# node_v2.net
KiCad netlist of a schematic drawn in EAGLE
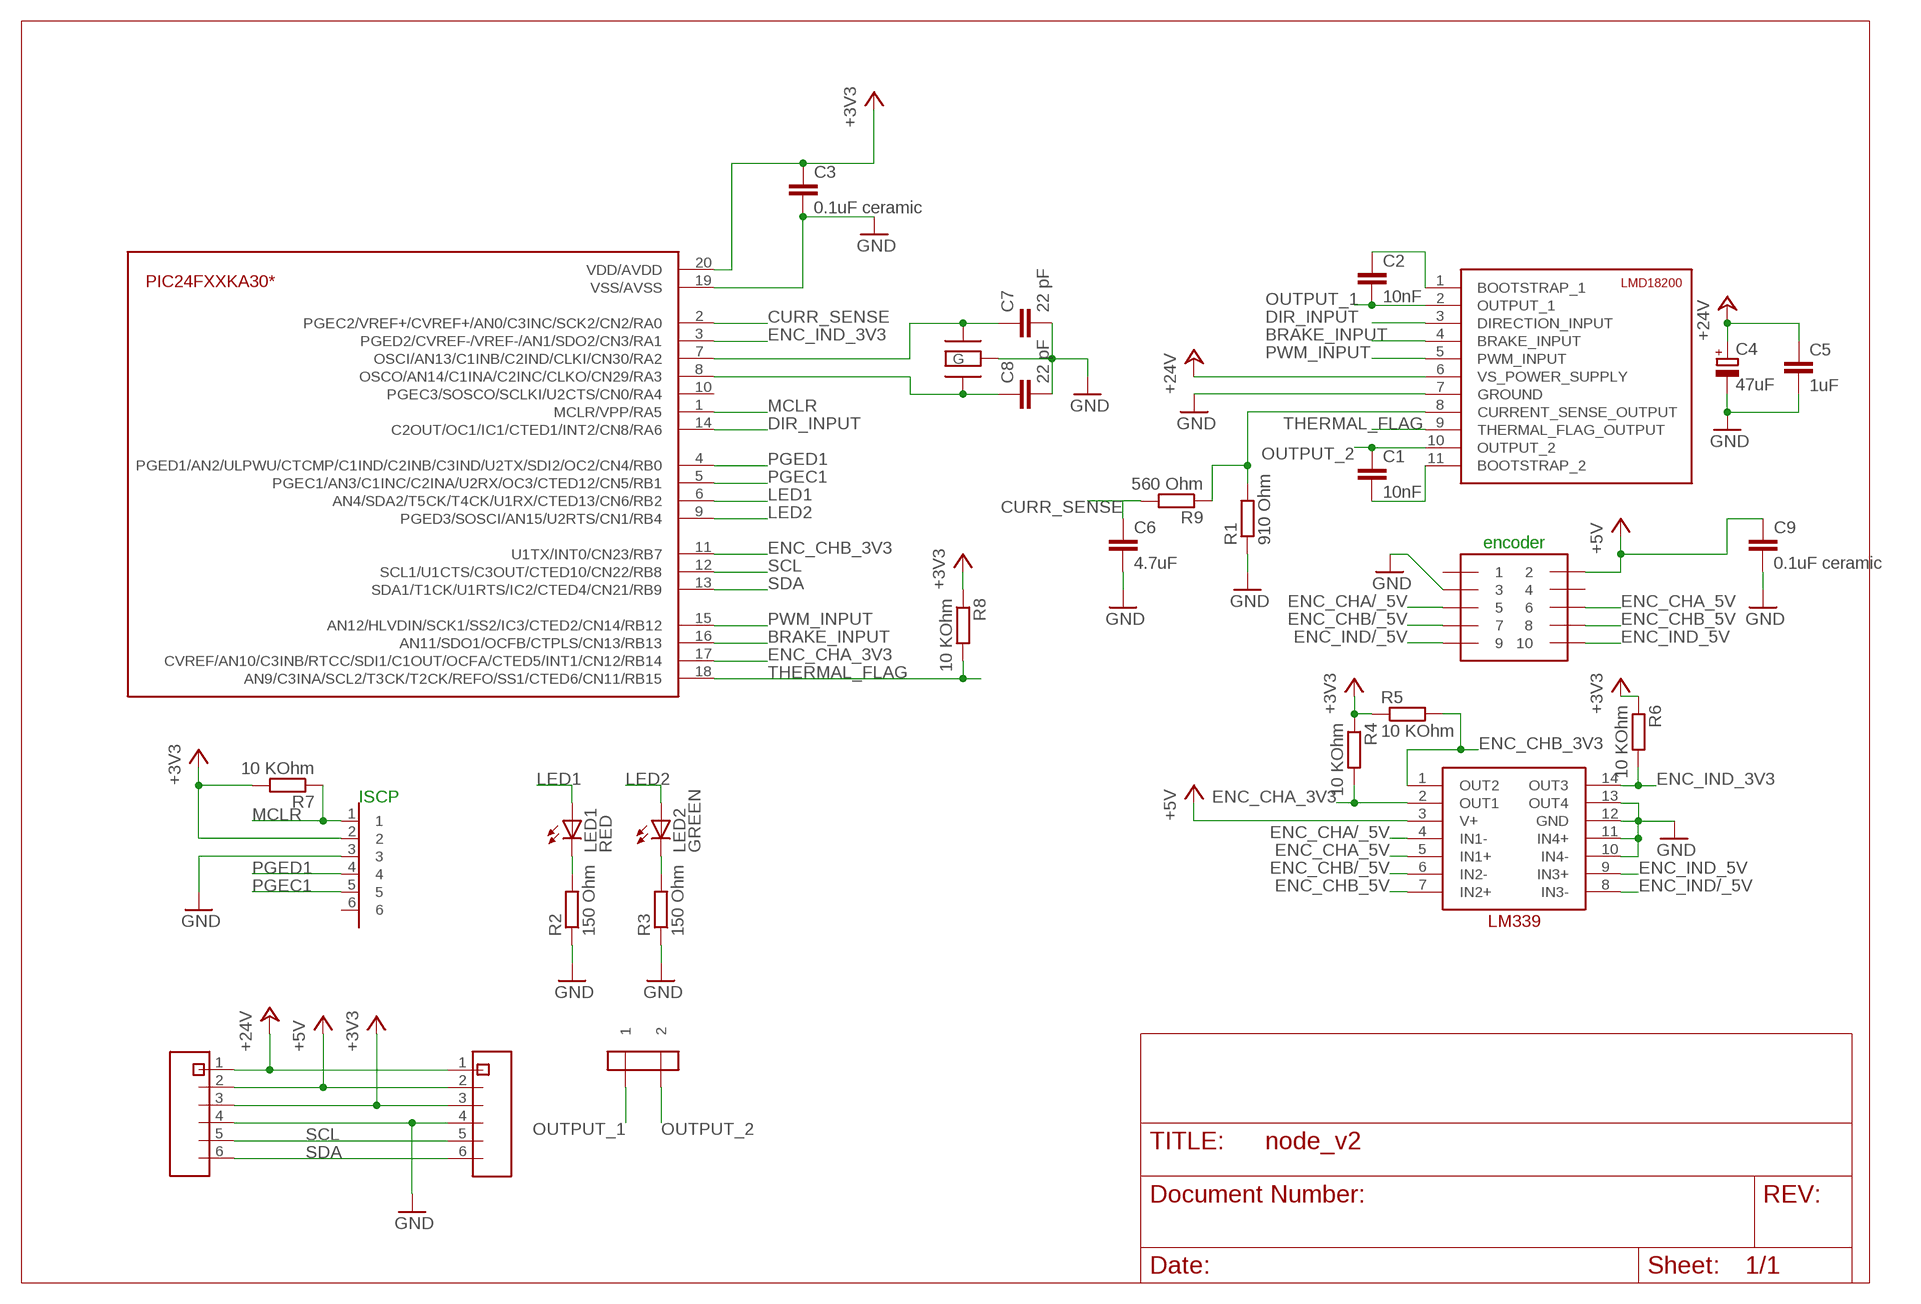
[diagram p0: schematic, sheet 1]

(export (version "E")
  (design (tool "Eeschema 10.0.6"))
  (components
    (comp (ref "C1")
      (value "10nF")
      (footprint "eagle-import:C0603")
      (libsource (lib "eagle-import") (part "resistor_C-EUC0603"))
    )
    (comp (ref "C2")
      (value "10nF")
      (footprint "eagle-import:C0603")
      (libsource (lib "eagle-import") (part "resistor_C-EUC0603"))
    )
    (comp (ref "C3")
      (value "0.1uF ceramic")
      (footprint "eagle-import:C0805K")
      (libsource (lib "eagle-import") (part "resistor_C-EUC0805K"))
    )
    (comp (ref "C4")
      (value "47uF")
      (footprint "eagle-import:E5-10,5")
      (libsource (lib "eagle-import") (part "CPOL-EUE5-10.5"))
    )
    (comp (ref "C5")
      (value "1uF")
      (footprint "eagle-import:C050-025X075")
      (libsource (lib "eagle-import") (part "C-EU050-025X075"))
    )
    (comp (ref "C6")
      (value "4.7uF")
      (footprint "eagle-import:C0805K")
      (libsource (lib "eagle-import") (part "resistor_C-EUC0805K"))
    )
    (comp (ref "C7")
      (value "22 pF")
      (footprint "eagle-import:C0603")
      (libsource (lib "eagle-import") (part "C-EUC0603"))
    )
    (comp (ref "C8")
      (value "22 pF")
      (footprint "eagle-import:C0603")
      (libsource (lib "eagle-import") (part "C-EUC0603"))
    )
    (comp (ref "C9")
      (value "0.1uF ceramic")
      (footprint "eagle-import:C0805K")
      (libsource (lib "eagle-import") (part "resistor_C-EUC0805K"))
    )
    (comp (ref "LED1")
      (value "RED")
      (footprint "eagle-import:CHIPLED_1206")
      (libsource (lib "eagle-import") (part "LEDCHIPLED_1206"))
    )
    (comp (ref "LED2")
      (value "GREEN")
      (footprint "eagle-import:CHIPLED_1206")
      (libsource (lib "eagle-import") (part "LEDCHIPLED_1206"))
    )
    (comp (ref "R1")
      (value "910 Ohm")
      (footprint "eagle-import:R0603")
      (libsource (lib "eagle-import") (part "R-EU_R0603"))
    )
    (comp (ref "R2")
      (value "150 Ohm")
      (footprint "eagle-import:R0603")
      (libsource (lib "eagle-import") (part "R-EU_R0603"))
    )
    (comp (ref "R3")
      (value "150 Ohm")
      (footprint "eagle-import:R0603")
      (libsource (lib "eagle-import") (part "R-EU_R0603"))
    )
    (comp (ref "R4")
      (value "10 KOhm")
      (footprint "eagle-import:R0603")
      (libsource (lib "eagle-import") (part "R-EU_R0603"))
    )
    (comp (ref "R5")
      (value "10 KOhm")
      (footprint "eagle-import:R0603")
      (libsource (lib "eagle-import") (part "R-EU_R0603"))
    )
    (comp (ref "R6")
      (value "10 KOhm")
      (footprint "eagle-import:R0603")
      (libsource (lib "eagle-import") (part "R-EU_R0603"))
    )
    (comp (ref "R7")
      (value "10 KOhm")
      (footprint "eagle-import:R0603")
      (libsource (lib "eagle-import") (part "R-EU_R0603"))
    )
    (comp (ref "R8")
      (value "10 KOhm")
      (footprint "eagle-import:R0603")
      (libsource (lib "eagle-import") (part "R-EU_R0603"))
    )
    (comp (ref "R9")
      (value "560 Ohm")
      (footprint "eagle-import:R0603")
      (libsource (lib "eagle-import") (part "R-EU_R0603"))
    )
    (comp (ref "U$1")
      (value "PIC24F32KA301")
      (footprint "eagle-import:SSOP-20")
      (libsource (lib "eagle-import") (part "PIC24F32KA301"))
    )
    (comp (ref "U$2")
      (value "LMD18200")
      (footprint "eagle-import:TO-220-11")
      (libsource (lib "eagle-import") (part "LMD18200"))
    )
    (comp (ref "U$3")
      (value "MOLEX_3.96MM_6P")
      (footprint "eagle-import:MOLEX_3.96MM_6P")
      (libsource (lib "eagle-import") (part "MOLEX_3.96MM_6P"))
    )
    (comp (ref "U$4")
      (value "MOLEX_3.96MM_6P")
      (footprint "eagle-import:MOLEX_3.96MM_6P")
      (libsource (lib "eagle-import") (part "MOLEX_3.96MM_6P"))
    )
    (comp (ref "U$5")
      (value "DIN41651_10P")
      (footprint "eagle-import:DIN41651_10P")
      (libsource (lib "eagle-import") (part "DIN41651_10P"))
    )
    (comp (ref "U$6")
      (value "STIFTLIST_6X1P")
      (footprint "eagle-import:STIFTLIST_6X1P")
      (libsource (lib "eagle-import") (part "STIFTLIST_6X1P"))
    )
    (comp (ref "U$7")
      (value "CRYSTAL_ELFA")
      (footprint "eagle-import:CRYSTAL_SMD")
      (libsource (lib "eagle-import") (part "CRYSTAL_ELFA"))
    )
    (comp (ref "U$8")
      (value "PCB_SKRUVPLINT_2P")
      (footprint "eagle-import:PCB_SKRUVPLINT_2P")
      (libsource (lib "eagle-import") (part "PCB_SKRUVPLINT_2P"))
    )
    (comp (ref "U$9")
      (value "LM339")
      (footprint "eagle-import:SO14")
      (libsource (lib "eagle-import") (part "LM339"))
    )
  )
  (nets
    (net (code "1") (name "+3V3") (class "Default")
      (node (ref "C3") (pin "1") (pinfunction "1_1") (pintype "passive"))
      (node (ref "R4") (pin "1") (pinfunction "1_1") (pintype "passive"))
      (node (ref "R5") (pin "1") (pinfunction "1_1") (pintype "passive"))
      (node (ref "R6") (pin "1") (pinfunction "1_1") (pintype "passive"))
      (node (ref "R7") (pin "2") (pinfunction "2_2") (pintype "passive"))
      (node (ref "R8") (pin "1") (pinfunction "1_1") (pintype "passive"))
      (node (ref "U$1") (pin "20") (pinfunction "VDD/AVDD_20") (pintype "bidirectional"))
      (node (ref "U$3") (pin "3") (pinfunction "3_3") (pintype "bidirectional"))
      (node (ref "U$4") (pin "3") (pinfunction "3_3") (pintype "bidirectional"))
      (node (ref "U$6") (pin "2") (pinfunction "2_2") (pintype "bidirectional"))
    )
    (net (code "2") (name "+5V") (class "Default")
      (node (ref "C9") (pin "1") (pinfunction "1_1") (pintype "passive"))
      (node (ref "U$3") (pin "2") (pinfunction "2_2") (pintype "bidirectional"))
      (node (ref "U$4") (pin "2") (pinfunction "2_2") (pintype "bidirectional"))
      (node (ref "U$5") (pin "2") (pinfunction "2_2") (pintype "bidirectional"))
      (node (ref "U$9") (pin "3") (pinfunction "V+_3") (pintype "bidirectional"))
    )
    (net (code "3") (name "+24V") (class "Default")
      (node (ref "C4") (pin "+") (pinfunction "+_+") (pintype "passive"))
      (node (ref "C5") (pin "1") (pinfunction "1_1") (pintype "passive"))
      (node (ref "U$2") (pin "6") (pinfunction "VS_POWER_SUPPLY_6") (pintype "bidirectional"))
      (node (ref "U$3") (pin "1") (pinfunction "1_1") (pintype "bidirectional"))
      (node (ref "U$4") (pin "1") (pinfunction "1_1") (pintype "bidirectional"))
    )
    (net (code "4") (name "/BRAKE_INPUT") (class "Default")
      (node (ref "U$1") (pin "16") (pinfunction "AN11/SDO1/OCFB/CTPLS/CN13/RB13_16") (pintype "bidirectional"))
      (node (ref "U$2") (pin "4") (pinfunction "BRAKE_INPUT_4") (pintype "bidirectional"))
    )
    (net (code "5") (name "/CURR_SENSE") (class "Default")
      (node (ref "C6") (pin "1") (pinfunction "1_1") (pintype "passive"))
      (node (ref "R9") (pin "2") (pinfunction "2_2") (pintype "passive"))
      (node (ref "U$1") (pin "2") (pinfunction "PGEC2/VREF+/CVREF+/AN0/C3INC/SCK2/CN2/RA0_2") (pintype "bidirectional"))
    )
    (net (code "6") (name "/DIR_INPUT") (class "Default")
      (node (ref "U$1") (pin "14") (pinfunction "C2OUT/OC1/IC1/CTED1/INT2/CN8/RA6_14") (pintype "bidirectional"))
      (node (ref "U$2") (pin "3") (pinfunction "DIRECTION_INPUT_3") (pintype "bidirectional"))
    )
    (net (code "7") (name "/ENC_CHA_3V3") (class "Default")
      (node (ref "R4") (pin "2") (pinfunction "2_2") (pintype "passive"))
      (node (ref "U$1") (pin "17") (pinfunction "CVREF/AN10/C3INB/RTCC/SDI1/C1OUT/OCFA/CTED5/INT1/CN12/RB14_17") (pintype "bidirectional"))
      (node (ref "U$9") (pin "2") (pinfunction "OUT1_2") (pintype "bidirectional"))
    )
    (net (code "8") (name "/ENC_CHA_5V") (class "Default")
      (node (ref "U$5") (pin "6") (pinfunction "6_6") (pintype "bidirectional"))
      (node (ref "U$9") (pin "5") (pinfunction "IN1+_5") (pintype "bidirectional"))
    )
    (net (code "9") (name "/ENC_CHA{slash}_5V") (class "Default")
      (node (ref "U$5") (pin "5") (pinfunction "5_5") (pintype "bidirectional"))
      (node (ref "U$9") (pin "4") (pinfunction "IN1-_4") (pintype "bidirectional"))
    )
    (net (code "10") (name "/ENC_CHB_3V3") (class "Default")
      (node (ref "R5") (pin "2") (pinfunction "2_2") (pintype "passive"))
      (node (ref "U$1") (pin "11") (pinfunction "U1TX/INT0/CN23/RB7_11") (pintype "bidirectional"))
      (node (ref "U$9") (pin "1") (pinfunction "OUT2_1") (pintype "bidirectional"))
    )
    (net (code "11") (name "/ENC_CHB_5V") (class "Default")
      (node (ref "U$5") (pin "8") (pinfunction "8_8") (pintype "bidirectional"))
      (node (ref "U$9") (pin "7") (pinfunction "IN2+_7") (pintype "bidirectional"))
    )
    (net (code "12") (name "/ENC_CHB{slash}_5V") (class "Default")
      (node (ref "U$5") (pin "7") (pinfunction "7_7") (pintype "bidirectional"))
      (node (ref "U$9") (pin "6") (pinfunction "IN2-_6") (pintype "bidirectional"))
    )
    (net (code "13") (name "/ENC_IND_3V3") (class "Default")
      (node (ref "R6") (pin "2") (pinfunction "2_2") (pintype "passive"))
      (node (ref "U$1") (pin "3") (pinfunction "PGED2/CVREF-/VREF-/AN1/SDO2/CN3/RA1_3") (pintype "bidirectional"))
      (node (ref "U$9") (pin "14") (pinfunction "OUT3_14") (pintype "bidirectional"))
    )
    (net (code "14") (name "/ENC_IND_5V") (class "Default")
      (node (ref "U$5") (pin "10") (pinfunction "10_10") (pintype "bidirectional"))
      (node (ref "U$9") (pin "9") (pinfunction "IN3+_9") (pintype "bidirectional"))
    )
    (net (code "15") (name "/ENC_IND{slash}_5V") (class "Default")
      (node (ref "U$5") (pin "9") (pinfunction "9_9") (pintype "bidirectional"))
      (node (ref "U$9") (pin "8") (pinfunction "IN3-_8") (pintype "bidirectional"))
    )
    (net (code "16") (name "/LED1") (class "Default")
      (node (ref "LED1") (pin "A") (pinfunction "A_A") (pintype "passive"))
      (node (ref "U$1") (pin "6") (pinfunction "AN4/SDA2/T5CK/T4CK/U1RX/CTED13/CN6/RB2_6") (pintype "bidirectional"))
    )
    (net (code "17") (name "/LED2") (class "Default")
      (node (ref "LED2") (pin "A") (pinfunction "A_A") (pintype "passive"))
      (node (ref "U$1") (pin "9") (pinfunction "PGED3/SOSCI/AN15/U2RTS/CN1/RB4_9") (pintype "bidirectional"))
    )
    (net (code "18") (name "/MCLR") (class "Default")
      (node (ref "R7") (pin "1") (pinfunction "1_1") (pintype "passive"))
      (node (ref "U$1") (pin "1") (pinfunction "MCLR/VPP/RA5_1") (pintype "bidirectional"))
      (node (ref "U$6") (pin "1") (pinfunction "1_1") (pintype "bidirectional"))
    )
    (net (code "19") (name "/OUTPUT_1") (class "Default")
      (node (ref "C2") (pin "2") (pinfunction "2_2") (pintype "passive"))
      (node (ref "U$2") (pin "2") (pinfunction "OUTPUT_1_2") (pintype "bidirectional"))
      (node (ref "U$8") (pin "1") (pinfunction "1_1") (pintype "bidirectional"))
    )
    (net (code "20") (name "/OUTPUT_2") (class "Default")
      (node (ref "C1") (pin "1") (pinfunction "1_1") (pintype "passive"))
      (node (ref "U$2") (pin "10") (pinfunction "OUTPUT_2_10") (pintype "bidirectional"))
      (node (ref "U$8") (pin "2") (pinfunction "2_2") (pintype "bidirectional"))
    )
    (net (code "21") (name "/PGEC1") (class "Default")
      (node (ref "U$1") (pin "5") (pinfunction "PGEC1/AN3/C1INC/C2INA/U2RX/OC3/CTED12/CN5/RB1_5") (pintype "bidirectional"))
      (node (ref "U$6") (pin "5") (pinfunction "5_5") (pintype "bidirectional"))
    )
    (net (code "22") (name "/PGED1") (class "Default")
      (node (ref "U$1") (pin "4") (pinfunction "PGED1/AN2/ULPWU/CTCMP/C1IND/C2INB/C3IND/U2TX/SDI2/OC2/CN4/RB0_4") (pintype "bidirectional"))
      (node (ref "U$6") (pin "4") (pinfunction "4_4") (pintype "bidirectional"))
    )
    (net (code "23") (name "/PWM_INPUT") (class "Default")
      (node (ref "U$1") (pin "15") (pinfunction "AN12/HLVDIN/SCK1/SS2/IC3/CTED2/CN14/RB12_15") (pintype "bidirectional"))
      (node (ref "U$2") (pin "5") (pinfunction "PWM_INPUT_5") (pintype "bidirectional"))
    )
    (net (code "24") (name "/SCL") (class "Default")
      (node (ref "U$1") (pin "12") (pinfunction "SCL1/U1CTS/C3OUT/CTED10/CN22/RB8_12") (pintype "bidirectional"))
      (node (ref "U$3") (pin "5") (pinfunction "5_5") (pintype "bidirectional"))
      (node (ref "U$4") (pin "5") (pinfunction "5_5") (pintype "bidirectional"))
    )
    (net (code "25") (name "/SDA") (class "Default")
      (node (ref "U$1") (pin "13") (pinfunction "SDA1/T1CK/U1RTS/IC2/CTED4/CN21/RB9_13") (pintype "bidirectional"))
      (node (ref "U$3") (pin "6") (pinfunction "6_6") (pintype "bidirectional"))
      (node (ref "U$4") (pin "6") (pinfunction "6_6") (pintype "bidirectional"))
    )
    (net (code "26") (name "/THERMAL_FLAG") (class "Default")
      (node (ref "R8") (pin "2") (pinfunction "2_2") (pintype "passive"))
      (node (ref "U$1") (pin "18") (pinfunction "AN9/C3INA/SCL2/T3CK/T2CK/REFO/SS1/CTED6/CN11/RB15_18") (pintype "bidirectional"))
      (node (ref "U$2") (pin "9") (pinfunction "THERMAL_FLAG_OUTPUT_9") (pintype "bidirectional"))
    )
    (net (code "27") (name "GND") (class "Default")
      (node (ref "C3") (pin "2") (pinfunction "2_2") (pintype "passive"))
      (node (ref "C4") (pin "-") (pinfunction "-_-") (pintype "passive"))
      (node (ref "C5") (pin "2") (pinfunction "2_2") (pintype "passive"))
      (node (ref "C6") (pin "2") (pinfunction "2_2") (pintype "passive"))
      (node (ref "C7") (pin "2") (pinfunction "2_2") (pintype "passive"))
      (node (ref "C8") (pin "2") (pinfunction "2_2") (pintype "passive"))
      (node (ref "C9") (pin "2") (pinfunction "2_2") (pintype "passive"))
      (node (ref "R1") (pin "1") (pinfunction "1_1") (pintype "passive"))
      (node (ref "R2") (pin "1") (pinfunction "1_1") (pintype "passive"))
      (node (ref "R3") (pin "1") (pinfunction "1_1") (pintype "passive"))
      (node (ref "U$1") (pin "19") (pinfunction "VSS/AVSS_19") (pintype "bidirectional"))
      (node (ref "U$2") (pin "7") (pinfunction "GROUND_7") (pintype "bidirectional"))
      (node (ref "U$3") (pin "4") (pinfunction "4_4") (pintype "bidirectional"))
      (node (ref "U$4") (pin "4") (pinfunction "4_4") (pintype "bidirectional"))
      (node (ref "U$5") (pin "3") (pinfunction "3_3") (pintype "bidirectional"))
      (node (ref "U$6") (pin "3") (pinfunction "3_3") (pintype "bidirectional"))
      (node (ref "U$7") (pin "2") (pinfunction "G_2") (pintype "bidirectional"))
      (node (ref "U$7") (pin "4") (pinfunction "G_4") (pintype "bidirectional"))
      (node (ref "U$9") (pin "10") (pinfunction "IN4-_10") (pintype "bidirectional"))
      (node (ref "U$9") (pin "11") (pinfunction "IN4+_11") (pintype "bidirectional"))
      (node (ref "U$9") (pin "12") (pinfunction "GND_12") (pintype "bidirectional"))
      (node (ref "U$9") (pin "13") (pinfunction "OUT4_13") (pintype "bidirectional"))
    )
    (net (code "28") (name "Net-(LED1-PadC)") (class "Default")
      (node (ref "LED1") (pin "C") (pinfunction "C_C") (pintype "passive"))
      (node (ref "R2") (pin "2") (pinfunction "2_2") (pintype "passive"))
    )
    (net (code "29") (name "Net-(LED2-PadC)") (class "Default")
      (node (ref "LED2") (pin "C") (pinfunction "C_C") (pintype "passive"))
      (node (ref "R3") (pin "2") (pinfunction "2_2") (pintype "passive"))
    )
    (net (code "30") (name "Net-(U$1-OSCI{slash}AN13{slash}C1INB{slash}C2IND{slash}CLKI{slash}CN30{slash}RA2)") (class "Default")
      (node (ref "C7") (pin "1") (pinfunction "1_1") (pintype "passive"))
      (node (ref "U$1") (pin "7") (pinfunction "OSCI/AN13/C1INB/C2IND/CLKI/CN30/RA2_7") (pintype "bidirectional"))
      (node (ref "U$7") (pin "3") (pinfunction "CRYSTAL_2_3") (pintype "bidirectional"))
    )
    (net (code "31") (name "Net-(U$1-OSCO{slash}AN14{slash}C1INA{slash}C2INC{slash}CLKO{slash}CN29{slash}RA3)") (class "Default")
      (node (ref "C8") (pin "1") (pinfunction "1_1") (pintype "passive"))
      (node (ref "U$1") (pin "8") (pinfunction "OSCO/AN14/C1INA/C2INC/CLKO/CN29/RA3_8") (pintype "bidirectional"))
      (node (ref "U$7") (pin "1") (pinfunction "CRYSTAL_1_1") (pintype "bidirectional"))
    )
    (net (code "32") (name "Net-(U$2-BOOTSTRAP_1)") (class "Default")
      (node (ref "C2") (pin "1") (pinfunction "1_1") (pintype "passive"))
      (node (ref "U$2") (pin "1") (pinfunction "BOOTSTRAP_1_1") (pintype "bidirectional"))
    )
    (net (code "33") (name "Net-(U$2-BOOTSTRAP_2)") (class "Default")
      (node (ref "C1") (pin "2") (pinfunction "2_2") (pintype "passive"))
      (node (ref "U$2") (pin "11") (pinfunction "BOOTSTRAP_2_11") (pintype "bidirectional"))
    )
    (net (code "34") (name "Net-(U$2-CURRENT_SENSE_OUTPUT)") (class "Default")
      (node (ref "R1") (pin "2") (pinfunction "2_2") (pintype "passive"))
      (node (ref "R9") (pin "1") (pinfunction "1_1") (pintype "passive"))
      (node (ref "U$2") (pin "8") (pinfunction "CURRENT_SENSE_OUTPUT_8") (pintype "bidirectional"))
    )
    (net (code "35") (name "unconnected-(U$1-PGEC3{slash}SOSCO{slash}SCLKI{slash}U2CTS{slash}CN0{slash}RA4-Pad10)") (class "Default")
      (node (ref "U$1") (pin "10") (pinfunction "PGEC3/SOSCO/SCLKI/U2CTS/CN0/RA4_10") (pintype "bidirectional"))
    )
    (net (code "36") (name "unconnected-(U$5-Pad1)") (class "Default")
      (node (ref "U$5") (pin "1") (pinfunction "1_1") (pintype "bidirectional"))
    )
    (net (code "37") (name "unconnected-(U$5-Pad4)") (class "Default")
      (node (ref "U$5") (pin "4") (pinfunction "4_4") (pintype "bidirectional"))
    )
    (net (code "38") (name "unconnected-(U$6-Pad6)") (class "Default")
      (node (ref "U$6") (pin "6") (pinfunction "6_6") (pintype "bidirectional"))
    )
  )
)
